# FPGA.net
KiCad netlist of a schematic drawn in Altium Designer
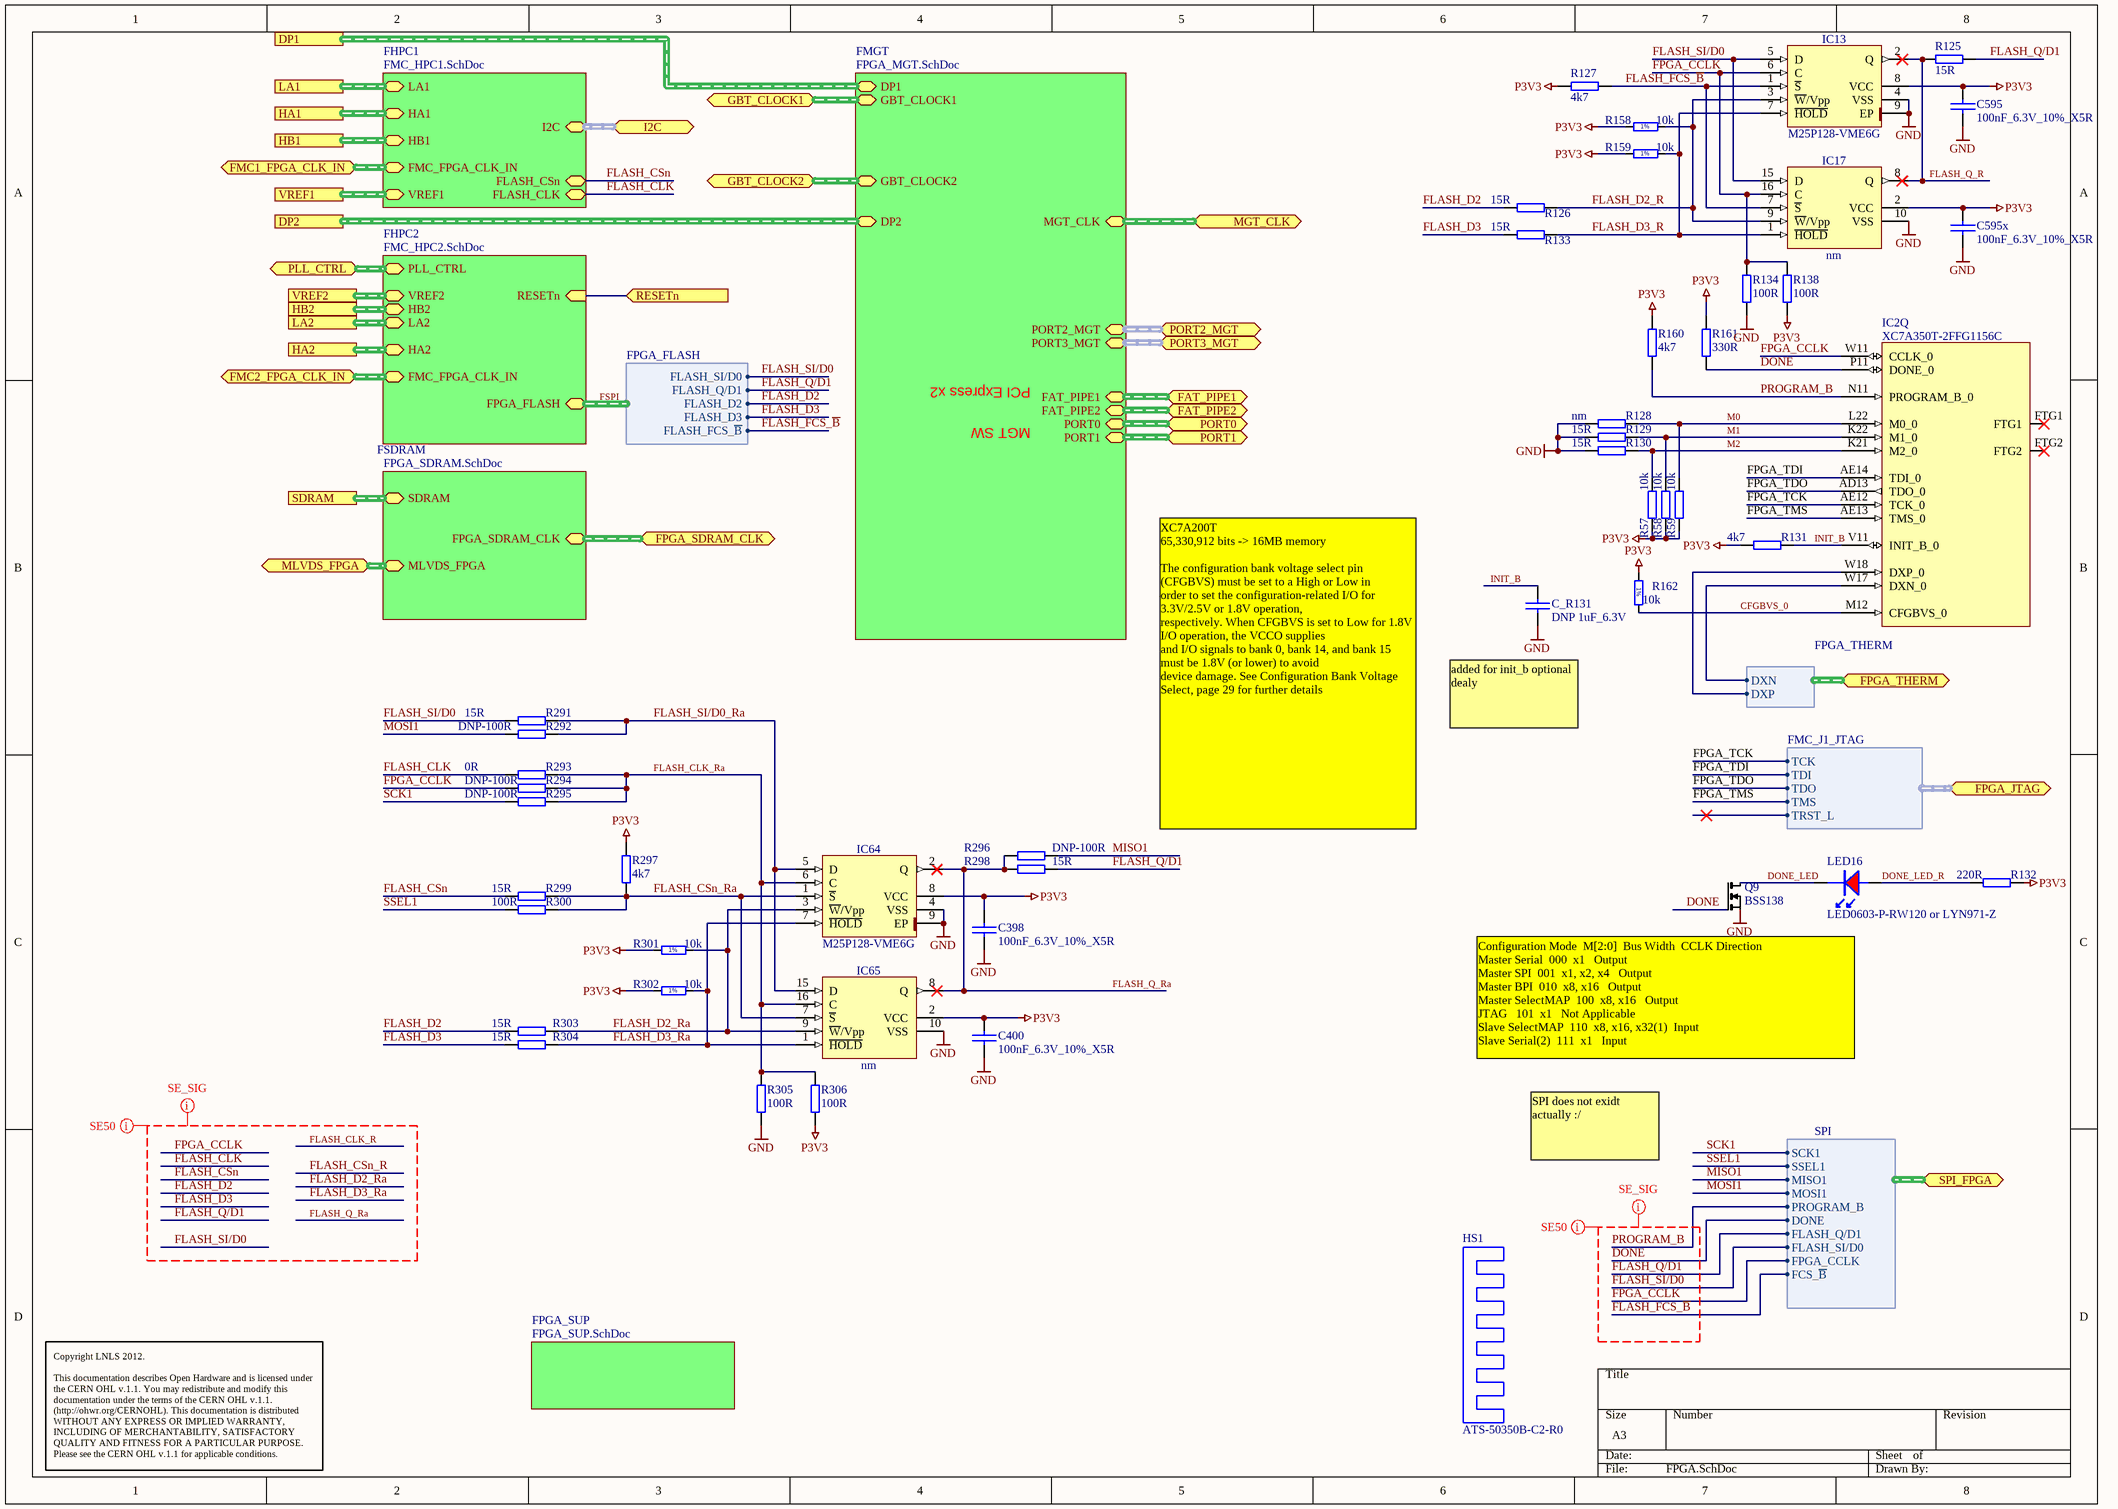
[diagram p0: FPGA.SchDoc]

(export (version "E")
  (design (tool "Eeschema 10.0.6"))
  (components
    (comp (ref "C398")
      (value "100nF_6.3V_10%_X5R")
      (footprint "0201C")
      (description "Capacitor SMD")
      (libsource (lib "LIBRARY_SCH") (part "CAP_SMD_0201"))
    )
    (comp (ref "C400")
      (value "100nF_6.3V_10%_X5R")
      (footprint "0201C")
      (description "Capacitor SMD")
      (libsource (lib "LIBRARY_SCH") (part "CAP_SMD_0201"))
    )
    (comp (ref "C595")
      (value "100nF_6.3V_10%_X5R")
      (footprint "0201C")
      (description "Capacitor SMD")
      (libsource (lib "LIBRARY_SCH") (part "CAP_SMD_0201"))
    )
    (comp (ref "C595x")
      (value "100nF_6.3V_10%_X5R")
      (footprint "0201C")
      (description "Capacitor SMD")
      (libsource (lib "LIBRARY_SCH") (part "CAP_SMD_0201"))
    )
    (comp (ref "C_R131")
      (value "DNP 1uF_6.3V")
      (footprint "0603C")
      (description "Capacitor SMD")
      (libsource (lib "LIBRARY_SCH") (part "CAP_SMD_0603"))
    )
    (comp (ref "HS1")
      (value "ATS-50350B-C2-R0")
      (footprint "HEAT_SINK_ATS-50350B-C2-R0")
      (description "Heat sink BGA 35x35(44.9)mm")
      (libsource (lib "LIBRARY_SCH") (part "HEAT_SINK_ATS-50350B-C2-R0"))
    )
    (comp (ref "IC2")
      (value "XC7A350T-2FFG1156C")
      (footprint "BGA1156C100P34X34_3500X3500X335")
      (description "Artix-6 FPGA, 16 GTPs, 600 User I/Os, 1156-Pin BGA, Speed Grade 2, Commercial Grade, Pb-Free")
      (fields (field (name "MANUFACTURER") "XILINX") (field (name "AUTHOR") "CERN DEM JLC"))
      (libsource (lib "AMC_FMC_Carrier") (part "XC7A350T-2FFG1156C"))
    )
    (comp (ref "IC13")
      (value "M25P128-VME6G")
      (footprint "PSON127P800X600X100-9N-R640X480")
      (description "128 Mbit (Multilevel), low-voltage, Serial Flash memory with 50-MHz SPI bus interface")
      (fields (field (name "MANUFACTURER") "NUMONYX") (field (name "AUTHOR") "CERN DEM JLC"))
      (libsource (lib "ICs And Semiconductors") (part "M25P128-VME"))
    )
    (comp (ref "IC17")
      (value "nm")
      (footprint "SOIC127P1030X265-16N")
      (description "128 Mbit (Multilevel), low-voltage, Serial Flash memory with 50-MHz SPI bus interface")
      (fields
        (field (name "PART NUMBER") "M25P128-VMF6G")
        (field (name "MANUFACTURER") "NUMONYX")
        (field (name "AUTHOR") "CERN DEM JLC")
      )
      (libsource (lib "ICs And Semiconductors") (part "M25P128-VMF"))
    )
    (comp (ref "IC64")
      (value "M25P128-VME6G")
      (footprint "PSON127P800X600X100-9N-R640X480")
      (description "128 Mbit (Multilevel), low-voltage, Serial Flash memory with 50-MHz SPI bus interface")
      (fields (field (name "MANUFACTURER") "NUMONYX") (field (name "AUTHOR") "CERN DEM JLC"))
      (libsource (lib "ICs And Semiconductors") (part "M25P128-VME"))
    )
    (comp (ref "IC65")
      (value "nm")
      (footprint "SOIC127P1030X265-16N")
      (description "128 Mbit (Multilevel), low-voltage, Serial Flash memory with 50-MHz SPI bus interface")
      (fields
        (field (name "PART NUMBER") "M25P128-VMF6G")
        (field (name "MANUFACTURER") "NUMONYX")
        (field (name "AUTHOR") "CERN DEM JLC")
      )
      (libsource (lib "ICs And Semiconductors") (part "M25P128-VMF"))
    )
    (comp (ref "LED16")
      (value "LED0603-P-RW120 or LYN971-Z")
      (footprint "led_0603R")
      (description "LED 0603 red")
      (libsource (lib "LIBRARY_SCH") (part "LED_0603R"))
    )
    (comp (ref "Q9") (value "BSS138") (footprint "SOT-23") (libsource (lib "LIBRARY_SCH") (part "Q_BSS138")))
    (comp (ref "R57")
      (value "10k")
      (footprint "0402R")
      (description "SMD Resistor")
      (libsource (lib "LIBRARY_SCH") (part "RES_0402"))
    )
    (comp (ref "R58")
      (value "10k")
      (footprint "0402R")
      (description "SMD Resistor")
      (libsource (lib "LIBRARY_SCH") (part "RES_0402"))
    )
    (comp (ref "R59")
      (value "10k")
      (footprint "0402R")
      (description "SMD Resistor")
      (libsource (lib "LIBRARY_SCH") (part "RES_0402"))
    )
    (comp (ref "R125")
      (value "15R")
      (footprint "0402R")
      (description "SMD Resistor")
      (libsource (lib "LIBRARY_SCH") (part "RES_0402"))
    )
    (comp (ref "R126")
      (value "15R")
      (footprint "0402R")
      (description "SMD Resistor")
      (libsource (lib "LIBRARY_SCH") (part "RES_0402"))
    )
    (comp (ref "R127")
      (value "4k7")
      (footprint "0402R")
      (description "SMD Resistor")
      (libsource (lib "LIBRARY_SCH") (part "RES_0402"))
    )
    (comp (ref "R128")
      (value "nm")
      (footprint "0402R")
      (description "SMD Resistor")
      (libsource (lib "LIBRARY_SCH") (part "RES_0402"))
    )
    (comp (ref "R129")
      (value "15R")
      (footprint "0402R")
      (description "SMD Resistor")
      (libsource (lib "LIBRARY_SCH") (part "RES_0402"))
    )
    (comp (ref "R130")
      (value "15R")
      (footprint "0402R")
      (description "SMD Resistor")
      (libsource (lib "LIBRARY_SCH") (part "RES_0402"))
    )
    (comp (ref "R131")
      (value "4k7")
      (footprint "0402R")
      (description "SMD Resistor")
      (libsource (lib "LIBRARY_SCH") (part "RES_0402"))
    )
    (comp (ref "R132")
      (value "220R")
      (footprint "0402R")
      (description "SMD Resistor")
      (libsource (lib "LIBRARY_SCH") (part "RES_0402"))
    )
    (comp (ref "R133")
      (value "15R")
      (footprint "0402R")
      (description "SMD Resistor")
      (libsource (lib "LIBRARY_SCH") (part "RES_0402"))
    )
    (comp (ref "R134")
      (value "100R")
      (footprint "0402R")
      (description "SMD Resistor")
      (libsource (lib "LIBRARY_SCH") (part "RES_0402"))
    )
    (comp (ref "R138")
      (value "100R")
      (footprint "0402R")
      (description "SMD Resistor")
      (libsource (lib "LIBRARY_SCH") (part "RES_0402"))
    )
    (comp (ref "R158")
      (value "10k")
      (footprint "0402R")
      (description "Resistor - 1%")
      (fields
        (field (name "PART NUMBER") "R0603_10K_1%_0.1W_100PPM")
        (field (name "POWER") "0.1W")
        (field (name "AUTHOR") "CERN DEM JLC")
      )
      (libsource (lib "Resistors") (part "Resistor - 1%"))
    )
    (comp (ref "R159")
      (value "10k")
      (footprint "0402R")
      (description "Resistor - 1%")
      (fields
        (field (name "PART NUMBER") "R0603_10K_1%_0.1W_100PPM")
        (field (name "POWER") "0.1W")
        (field (name "AUTHOR") "CERN DEM JLC")
      )
      (libsource (lib "Resistors") (part "Resistor - 1%"))
    )
    (comp (ref "R160")
      (value "4k7")
      (footprint "0402R")
      (description "SMD Resistor")
      (libsource (lib "LIBRARY_SCH") (part "RES_0402"))
    )
    (comp (ref "R161")
      (value "330R")
      (footprint "0402R")
      (description "SMD Resistor")
      (libsource (lib "LIBRARY_SCH") (part "RES_0402"))
    )
    (comp (ref "R162")
      (value "10k")
      (footprint "0402R")
      (description "Resistor - 1%")
      (fields
        (field (name "PART NUMBER") "R0603_10K_1%_0.1W_100PPM")
        (field (name "POWER") "0.1W")
        (field (name "AUTHOR") "CERN DEM JLC")
      )
      (libsource (lib "Resistors") (part "Resistor - 1%"))
    )
    (comp (ref "R291")
      (value "15R")
      (footprint "0402R")
      (description "SMD Resistor")
      (libsource (lib "LIBRARY_SCH") (part "RES_0402"))
    )
    (comp (ref "R292")
      (value "DNP-100R")
      (footprint "0402R")
      (description "SMD Resistor")
      (libsource (lib "LIBRARY_SCH") (part "RES_0402"))
    )
    (comp (ref "R293")
      (value "0R")
      (footprint "0402R")
      (description "SMD Resistor")
      (libsource (lib "LIBRARY_SCH") (part "RES_0402"))
    )
    (comp (ref "R294")
      (value "DNP-100R")
      (footprint "0402R")
      (description "SMD Resistor")
      (libsource (lib "LIBRARY_SCH") (part "RES_0402"))
    )
    (comp (ref "R295")
      (value "DNP-100R")
      (footprint "0402R")
      (description "SMD Resistor")
      (libsource (lib "LIBRARY_SCH") (part "RES_0402"))
    )
    (comp (ref "R296")
      (value "DNP-100R")
      (footprint "0402R")
      (description "SMD Resistor")
      (libsource (lib "LIBRARY_SCH") (part "RES_0402"))
    )
    (comp (ref "R297")
      (value "4k7")
      (footprint "0402R")
      (description "SMD Resistor")
      (libsource (lib "LIBRARY_SCH") (part "RES_0402"))
    )
    (comp (ref "R298")
      (value "15R")
      (footprint "0402R")
      (description "SMD Resistor")
      (libsource (lib "LIBRARY_SCH") (part "RES_0402"))
    )
    (comp (ref "R299")
      (value "15R")
      (footprint "0402R")
      (description "SMD Resistor")
      (libsource (lib "LIBRARY_SCH") (part "RES_0402"))
    )
    (comp (ref "R300")
      (value "100R")
      (footprint "0402R")
      (description "SMD Resistor")
      (libsource (lib "LIBRARY_SCH") (part "RES_0402"))
    )
    (comp (ref "R301")
      (value "10k")
      (footprint "0402R")
      (description "Resistor - 1%")
      (fields
        (field (name "PART NUMBER") "R0603_10K_1%_0.1W_100PPM")
        (field (name "POWER") "0.1W")
        (field (name "AUTHOR") "CERN DEM JLC")
      )
      (libsource (lib "Resistors") (part "Resistor - 1%"))
    )
    (comp (ref "R302")
      (value "10k")
      (footprint "0402R")
      (description "Resistor - 1%")
      (fields
        (field (name "PART NUMBER") "R0603_10K_1%_0.1W_100PPM")
        (field (name "POWER") "0.1W")
        (field (name "AUTHOR") "CERN DEM JLC")
      )
      (libsource (lib "Resistors") (part "Resistor - 1%"))
    )
    (comp (ref "R303")
      (value "15R")
      (footprint "0402R")
      (description "SMD Resistor")
      (libsource (lib "LIBRARY_SCH") (part "RES_0402"))
    )
    (comp (ref "R304")
      (value "15R")
      (footprint "0402R")
      (description "SMD Resistor")
      (libsource (lib "LIBRARY_SCH") (part "RES_0402"))
    )
    (comp (ref "R305")
      (value "100R")
      (footprint "0402R")
      (description "SMD Resistor")
      (libsource (lib "LIBRARY_SCH") (part "RES_0402"))
    )
    (comp (ref "R306")
      (value "100R")
      (footprint "0402R")
      (description "SMD Resistor")
      (libsource (lib "LIBRARY_SCH") (part "RES_0402"))
    )
  )
  (nets
    (net (code "12") (name "/CFGBVS_0") (class "Default")
      (node (ref "IC2") (pin "M12") (pinfunction "CFGBVS_0_M12") (pintype "input"))
      (node (ref "R162") (pin "2") (pinfunction "2_2") (pintype "passive"))
    )
    (net (code "13") (name "/DONE") (class "Default")
      (node (ref "IC2") (pin "P11") (pinfunction "DONE_0_P11") (pintype "bidirectional"))
      (node (ref "Q9") (pin "1") (pinfunction "G_1") (pintype "input"))
      (node (ref "R161") (pin "1") (pinfunction "1_1") (pintype "passive"))
    )
    (net (code "14") (name "/DONE_LED") (class "Default")
      (node (ref "LED16") (pin "K") (pinfunction "K_K") (pintype "passive"))
      (node (ref "Q9") (pin "3") (pinfunction "D_3") (pintype "passive"))
    )
    (net (code "15") (name "/DONE_LED_R") (class "Default")
      (node (ref "LED16") (pin "A") (pinfunction "A_A") (pintype "passive"))
      (node (ref "R132") (pin "1") (pinfunction "1_1") (pintype "passive"))
    )
    (net (code "18") (name "/DXN") (class "Default")
      (node (ref "IC2") (pin "W17") (pinfunction "DXN_0_W17") (pintype "input"))
    )
    (net (code "19") (name "/DXP") (class "Default")
      (node (ref "IC2") (pin "W18") (pinfunction "DXP_0_W18") (pintype "input"))
    )
    (net (code "24") (name "/FLASH_CLK") (class "Default")
      (node (ref "R293") (pin "1") (pinfunction "1_1") (pintype "passive"))
    )
    (net (code "26") (name "/FLASH_CLK_Ra") (class "Default")
      (node (ref "IC64") (pin "6") (pinfunction "C_6") (pintype "input"))
      (node (ref "IC65") (pin "16") (pinfunction "C_16") (pintype "input"))
      (node (ref "R293") (pin "2") (pinfunction "2_2") (pintype "passive"))
      (node (ref "R294") (pin "2") (pinfunction "2_2") (pintype "passive"))
      (node (ref "R295") (pin "2") (pinfunction "2_2") (pintype "passive"))
      (node (ref "R305") (pin "2") (pinfunction "2_2") (pintype "passive"))
      (node (ref "R306") (pin "2") (pinfunction "2_2") (pintype "passive"))
    )
    (net (code "27") (name "/FLASH_CSn") (class "Default")
      (node (ref "R299") (pin "1") (pinfunction "1_1") (pintype "passive"))
    )
    (net (code "29") (name "/FLASH_CSn_Ra") (class "Default")
      (node (ref "IC64") (pin "1") (pinfunction "~{S}_1") (pintype "input"))
      (node (ref "IC65") (pin "7") (pinfunction "~{S}_7") (pintype "input"))
      (node (ref "R297") (pin "1") (pinfunction "1_1") (pintype "passive"))
      (node (ref "R299") (pin "2") (pinfunction "2_2") (pintype "passive"))
      (node (ref "R300") (pin "2") (pinfunction "2_2") (pintype "passive"))
    )
    (net (code "30") (name "/FLASH_D2") (class "Default")
      (node (ref "R126") (pin "1") (pinfunction "1_1") (pintype "passive"))
      (node (ref "R303") (pin "1") (pinfunction "1_1") (pintype "passive"))
    )
    (net (code "31") (name "/FLASH_D2_R") (class "Default")
      (node (ref "IC13") (pin "3") (pinfunction "~{W}/Vpp_3") (pintype "input"))
      (node (ref "IC17") (pin "9") (pinfunction "~{W}/Vpp_9") (pintype "input"))
      (node (ref "R126") (pin "2") (pinfunction "2_2") (pintype "passive"))
      (node (ref "R158") (pin "2") (pinfunction "2_2") (pintype "passive"))
    )
    (net (code "32") (name "/FLASH_D2_Ra") (class "Default")
      (node (ref "IC64") (pin "3") (pinfunction "~{W}/Vpp_3") (pintype "input"))
      (node (ref "IC65") (pin "9") (pinfunction "~{W}/Vpp_9") (pintype "input"))
      (node (ref "R301") (pin "2") (pinfunction "2_2") (pintype "passive"))
      (node (ref "R303") (pin "2") (pinfunction "2_2") (pintype "passive"))
    )
    (net (code "33") (name "/FLASH_D3") (class "Default")
      (node (ref "R133") (pin "1") (pinfunction "1_1") (pintype "passive"))
      (node (ref "R304") (pin "1") (pinfunction "1_1") (pintype "passive"))
    )
    (net (code "34") (name "/FLASH_D3_R") (class "Default")
      (node (ref "IC13") (pin "7") (pinfunction "~{HOLD}_7") (pintype "input"))
      (node (ref "IC17") (pin "1") (pinfunction "~{HOLD}_1") (pintype "input"))
      (node (ref "R133") (pin "2") (pinfunction "2_2") (pintype "passive"))
      (node (ref "R159") (pin "2") (pinfunction "2_2") (pintype "passive"))
    )
    (net (code "35") (name "/FLASH_D3_Ra") (class "Default")
      (node (ref "IC64") (pin "7") (pinfunction "~{HOLD}_7") (pintype "input"))
      (node (ref "IC65") (pin "1") (pinfunction "~{HOLD}_1") (pintype "input"))
      (node (ref "R302") (pin "2") (pinfunction "2_2") (pintype "passive"))
      (node (ref "R304") (pin "2") (pinfunction "2_2") (pintype "passive"))
    )
    (net (code "36") (name "/FLASH_FCS_~{B}") (class "Default")
      (node (ref "IC13") (pin "1") (pinfunction "~{S}_1") (pintype "input"))
      (node (ref "IC17") (pin "7") (pinfunction "~{S}_7") (pintype "input"))
      (node (ref "R127") (pin "1") (pinfunction "1_1") (pintype "passive"))
    )
    (net (code "37") (name "/FLASH_Q_R") (class "Default")
      (node (ref "IC13") (pin "2") (pinfunction "Q_2") (pintype "output"))
      (node (ref "IC17") (pin "8") (pinfunction "Q_8") (pintype "output"))
      (node (ref "R125") (pin "1") (pinfunction "1_1") (pintype "passive"))
    )
    (net (code "38") (name "/FLASH_Q_Ra") (class "Default")
      (node (ref "IC64") (pin "2") (pinfunction "Q_2") (pintype "output"))
      (node (ref "IC65") (pin "8") (pinfunction "Q_8") (pintype "output"))
      (node (ref "R296") (pin "1") (pinfunction "1_1") (pintype "passive"))
      (node (ref "R298") (pin "1") (pinfunction "1_1") (pintype "passive"))
    )
    (net (code "39") (name "/FLASH_Q{slash}D1") (class "Default")
      (node (ref "R125") (pin "2") (pinfunction "2_2") (pintype "passive"))
      (node (ref "R298") (pin "2") (pinfunction "2_2") (pintype "passive"))
    )
    (net (code "40") (name "/FLASH_SI{slash}D0") (class "Default")
      (node (ref "IC13") (pin "5") (pinfunction "D_5") (pintype "input"))
      (node (ref "IC17") (pin "15") (pinfunction "D_15") (pintype "input"))
      (node (ref "R291") (pin "1") (pinfunction "1_1") (pintype "passive"))
    )
    (net (code "41") (name "/FLASH_SI{slash}D0_Ra") (class "Default")
      (node (ref "IC64") (pin "5") (pinfunction "D_5") (pintype "input"))
      (node (ref "IC65") (pin "15") (pinfunction "D_15") (pintype "input"))
      (node (ref "R291") (pin "2") (pinfunction "2_2") (pintype "passive"))
      (node (ref "R292") (pin "2") (pinfunction "2_2") (pintype "passive"))
    )
    (net (code "44") (name "/FPGA_CCLK") (class "Default")
      (node (ref "IC13") (pin "6") (pinfunction "C_6") (pintype "input"))
      (node (ref "IC17") (pin "16") (pinfunction "C_16") (pintype "input"))
      (node (ref "IC2") (pin "W11") (pinfunction "CCLK_0_W11") (pintype "bidirectional"))
      (node (ref "R134") (pin "2") (pinfunction "2_2") (pintype "passive"))
      (node (ref "R138") (pin "2") (pinfunction "2_2") (pintype "passive"))
      (node (ref "R294") (pin "1") (pinfunction "1_1") (pintype "passive"))
    )
    (net (code "47") (name "/FPGA_TCK") (class "Default")
      (node (ref "IC2") (pin "AE12") (pinfunction "TCK_0_AE12") (pintype "input"))
    )
    (net (code "48") (name "/FPGA_TDI") (class "Default")
      (node (ref "IC2") (pin "AE14") (pinfunction "TDI_0_AE14") (pintype "input"))
    )
    (net (code "49") (name "/FPGA_TDO") (class "Default")
      (node (ref "IC2") (pin "AD13") (pinfunction "TDO_0_AD13") (pintype "output"))
    )
    (net (code "50") (name "/FPGA_TMS") (class "Default")
      (node (ref "IC2") (pin "AE13") (pinfunction "TMS_0_AE13") (pintype "input"))
    )
    (net (code "59") (name "/INIT_B") (class "Default")
      (node (ref "C_R131") (pin "2") (pinfunction "2_2") (pintype "passive"))
      (node (ref "IC2") (pin "V11") (pinfunction "INIT_B_0_V11") (pintype "bidirectional"))
      (node (ref "R131") (pin "2") (pinfunction "2_2") (pintype "passive"))
    )
    (net (code "62") (name "/M0") (class "Default")
      (node (ref "IC2") (pin "L22") (pinfunction "M0_0_L22") (pintype "input"))
      (node (ref "R128") (pin "2") (pinfunction "2_2") (pintype "passive"))
      (node (ref "R59") (pin "2") (pinfunction "2_2") (pintype "passive"))
    )
    (net (code "63") (name "/M1") (class "Default")
      (node (ref "IC2") (pin "K22") (pinfunction "M1_0_K22") (pintype "input"))
      (node (ref "R129") (pin "2") (pinfunction "2_2") (pintype "passive"))
      (node (ref "R58") (pin "2") (pinfunction "2_2") (pintype "passive"))
    )
    (net (code "64") (name "/M2") (class "Default")
      (node (ref "IC2") (pin "K21") (pinfunction "M2_0_K21") (pintype "input"))
      (node (ref "R130") (pin "2") (pinfunction "2_2") (pintype "passive"))
      (node (ref "R57") (pin "2") (pinfunction "2_2") (pintype "passive"))
    )
    (net (code "67") (name "/MISO1") (class "Default")
      (node (ref "R296") (pin "2") (pinfunction "2_2") (pintype "passive"))
    )
    (net (code "69") (name "/MOSI1") (class "Default")
      (node (ref "R292") (pin "1") (pinfunction "1_1") (pintype "passive"))
    )
    (net (code "77") (name "/PROGRAM_B") (class "Default")
      (node (ref "IC2") (pin "N11") (pinfunction "PROGRAM_B_0_N11") (pintype "input"))
      (node (ref "R160") (pin "1") (pinfunction "1_1") (pintype "passive"))
    )
    (net (code "79") (name "/SCK1") (class "Default")
      (node (ref "R295") (pin "1") (pinfunction "1_1") (pintype "passive"))
    )
    (net (code "81") (name "/SSEL1") (class "Default")
      (node (ref "R300") (pin "1") (pinfunction "1_1") (pintype "passive"))
    )
    (net (code "88") (name "GND") (class "Default")
      (node (ref "C398") (pin "2") (pinfunction "2_2") (pintype "passive"))
      (node (ref "C400") (pin "2") (pinfunction "2_2") (pintype "passive"))
      (node (ref "C595") (pin "2") (pinfunction "2_2") (pintype "passive"))
      (node (ref "C595x") (pin "2") (pinfunction "2_2") (pintype "passive"))
      (node (ref "C_R131") (pin "1") (pinfunction "1_1") (pintype "passive"))
      (node (ref "IC13") (pin "4") (pinfunction "VSS_4") (pintype "power_in"))
      (node (ref "IC13") (pin "9") (pinfunction "EP_9") (pintype "power_in"))
      (node (ref "IC17") (pin "10") (pinfunction "VSS_10") (pintype "power_in"))
      (node (ref "IC64") (pin "4") (pinfunction "VSS_4") (pintype "power_in"))
      (node (ref "IC64") (pin "9") (pinfunction "EP_9") (pintype "power_in"))
      (node (ref "IC65") (pin "10") (pinfunction "VSS_10") (pintype "power_in"))
      (node (ref "Q9") (pin "2") (pinfunction "S_2") (pintype "passive"))
      (node (ref "R128") (pin "1") (pinfunction "1_1") (pintype "passive"))
      (node (ref "R129") (pin "1") (pinfunction "1_1") (pintype "passive"))
      (node (ref "R130") (pin "1") (pinfunction "1_1") (pintype "passive"))
      (node (ref "R134") (pin "1") (pinfunction "1_1") (pintype "passive"))
      (node (ref "R305") (pin "1") (pinfunction "1_1") (pintype "passive"))
    )
    (net (code "89") (name "P3V3") (class "Default")
      (node (ref "C398") (pin "1") (pinfunction "1_1") (pintype "passive"))
      (node (ref "C400") (pin "1") (pinfunction "1_1") (pintype "passive"))
      (node (ref "C595") (pin "1") (pinfunction "1_1") (pintype "passive"))
      (node (ref "C595x") (pin "1") (pinfunction "1_1") (pintype "passive"))
      (node (ref "IC13") (pin "8") (pinfunction "VCC_8") (pintype "power_in"))
      (node (ref "IC17") (pin "2") (pinfunction "VCC_2") (pintype "power_in"))
      (node (ref "IC64") (pin "8") (pinfunction "VCC_8") (pintype "power_in"))
      (node (ref "IC65") (pin "2") (pinfunction "VCC_2") (pintype "power_in"))
      (node (ref "R127") (pin "2") (pinfunction "2_2") (pintype "passive"))
      (node (ref "R131") (pin "1") (pinfunction "1_1") (pintype "passive"))
      (node (ref "R132") (pin "2") (pinfunction "2_2") (pintype "passive"))
      (node (ref "R138") (pin "1") (pinfunction "1_1") (pintype "passive"))
      (node (ref "R158") (pin "1") (pinfunction "1_1") (pintype "passive"))
      (node (ref "R159") (pin "1") (pinfunction "1_1") (pintype "passive"))
      (node (ref "R160") (pin "2") (pinfunction "2_2") (pintype "passive"))
      (node (ref "R161") (pin "2") (pinfunction "2_2") (pintype "passive"))
      (node (ref "R162") (pin "1") (pinfunction "1_1") (pintype "passive"))
      (node (ref "R297") (pin "2") (pinfunction "2_2") (pintype "passive"))
      (node (ref "R301") (pin "1") (pinfunction "1_1") (pintype "passive"))
      (node (ref "R302") (pin "1") (pinfunction "1_1") (pintype "passive"))
      (node (ref "R306") (pin "1") (pinfunction "1_1") (pintype "passive"))
      (node (ref "R57") (pin "1") (pinfunction "1_1") (pintype "passive"))
      (node (ref "R58") (pin "1") (pinfunction "1_1") (pintype "passive"))
      (node (ref "R59") (pin "1") (pinfunction "1_1") (pintype "passive"))
    )
    (net (code "90") (name "unconnected-(IC2-PadFTG1)") (class "Default")
      (node (ref "IC2") (pin "FTG1") (pinfunction "FTG1_FTG1") (pintype "passive+no_connect"))
    )
    (net (code "91") (name "unconnected-(IC2-PadFTG2)") (class "Default")
      (node (ref "IC2") (pin "FTG2") (pinfunction "FTG2_FTG2") (pintype "passive+no_connect"))
    )
  )
)
